# PwmOut.net
KiCad netlist of a schematic drawn in Altium Designer
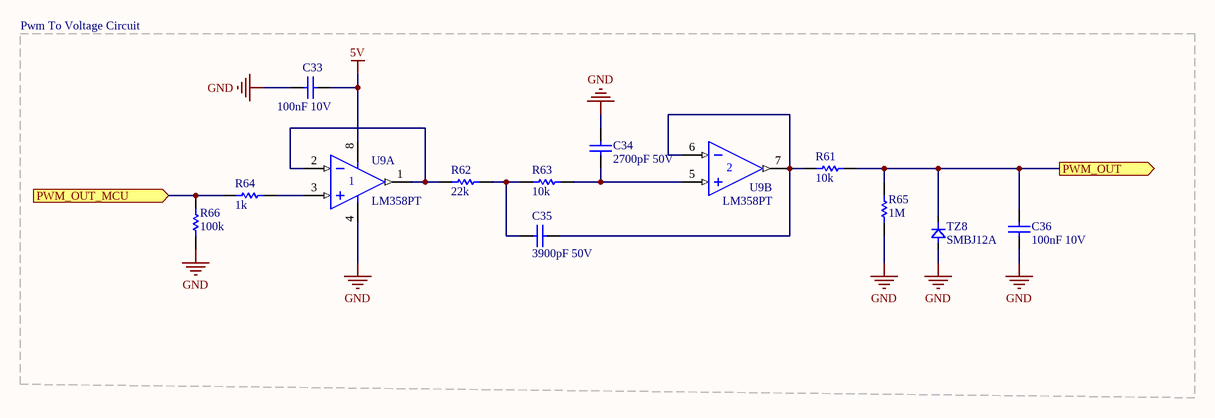
[diagram p0: PwmOut.SchDoc]

(export (version "E")
  (design (tool "Eeschema 10.0.6"))
  (components
    (comp (ref "C33")
      (value "100nF 10V")
      (footprint "0402")
      (description "Capacitor")
      (fields (field (name "PARTNUMBER") "CAP.100n.10V.20%.SMD.0402") (field (name "MANUFACTURER") "Wurth"))
      (libsource (lib "IntLib") (part "Cap"))
    )
    (comp (ref "C34")
      (value "2700pF 50V")
      (footprint "C0805")
      (description "Capacitor")
      (fields (field (name "PARTNUMBER") "CAP.2700p.50V.10%.SMD.0805") (field (name "MANUFACTURER") "Vishay"))
      (libsource (lib "IntLib") (part "Cap"))
    )
    (comp (ref "C35")
      (value "3900pF 50V")
      (footprint "C0805")
      (description "Capacitor")
      (fields (field (name "PARTNUMBER") "CAP.3900p.50V.5%.SMD.0805") (field (name "MANUFACTURER") "Vishay"))
      (libsource (lib "IntLib") (part "Cap"))
    )
    (comp (ref "C36")
      (value "100nF 10V")
      (footprint "C0805")
      (description "Capacitor")
      (fields (field (name "PARTNUMBER") "CAP.1u.10V.10%.SMD.0805") (field (name "MANUFACTURER") "Vishay"))
      (libsource (lib "IntLib") (part "Cap"))
    )
    (comp (ref "R61")
      (value "10k")
      (footprint "6-0805_M")
      (description "Resistor")
      (fields (field (name "PARTNUMBER") "RES.10K.1/8W.5%.SMD.0805") (field (name "MANUFACTURER") "Yageo"))
      (libsource (lib "IntLib") (part "Res"))
    )
    (comp (ref "R62")
      (value "22k")
      (footprint "6-0805_M")
      (description "Resistor")
      (fields (field (name "PARTNUMBER") "RES.22K.1/8W.5%.SMD.0805") (field (name "MANUFACTURER") "Bourns"))
      (libsource (lib "IntLib") (part "Res"))
    )
    (comp (ref "R63")
      (value "10k")
      (footprint "6-0805_M")
      (description "Resistor")
      (fields (field (name "PARTNUMBER") "RES.10K.1/8W.5%.SMD.0805") (field (name "MANUFACTURER") "Yageo"))
      (libsource (lib "IntLib") (part "Res"))
    )
    (comp (ref "R64")
      (value "1k")
      (footprint "6-0805_M")
      (description "Resistor")
      (fields (field (name "PARTNUMBER") "RES.1K.1/8W.5%.SMD.0805") (field (name "MANUFACTURER") "Yageo"))
      (libsource (lib "IntLib") (part "Res"))
    )
    (comp (ref "R65")
      (value "1M")
      (footprint "6-0805_M")
      (description "Resistor")
      (fields (field (name "PARTNUMBER") "RES.1M.1/8W.5%.SMD.0805") (field (name "MANUFACTURER") "Bourns"))
      (libsource (lib "IntLib") (part "Res"))
    )
    (comp (ref "R66")
      (value "100k")
      (footprint "6-0805_M")
      (description "Resistor")
      (fields (field (name "PARTNUMBER") "RES.100K.1/8W.5%.SMD.0805") (field (name "MANUFACTURER") "Yageo"))
      (libsource (lib "IntLib") (part "Res"))
    )
    (comp (ref "TZ8")
      (value "SMBJ12A")
      (footprint "DO-214AA")
      (description "ESD Suppressors / TVS Diodes 12V 600W SMB Unidirectional")
      (fields (field (name "MANUFACTURER") "ON Semiconductor"))
      (libsource (lib "IntLib") (part "SMBJ12A"))
    )
    (comp (ref "U9")
      (value "LM358PT")
      (footprint "TSOP-8")
      (description "Operational Amplifiers - Op Amps Dual Low Power")
      (fields (field (name "MANUFACTURER") "STMicroelectronics"))
      (libsource (lib "IntLib") (part "LM358PT"))
    )
  )
  (nets
    (net (code "1") (name "/PWM_OUT") (class "Default")
      (node (ref "C36") (pin "1") (pinfunction "1_1") (pintype "passive"))
      (node (ref "R61") (pin "2") (pinfunction "2_2") (pintype "passive"))
      (node (ref "R65") (pin "2") (pinfunction "2_2") (pintype "passive"))
      (node (ref "TZ8") (pin "2") (pinfunction "C_2") (pintype "passive"))
    )
    (net (code "2") (name "/PWM_OUT_MCU") (class "Default")
      (node (ref "R64") (pin "1") (pinfunction "1_1") (pintype "passive"))
      (node (ref "R66") (pin "2") (pinfunction "2_2") (pintype "passive"))
    )
    (net (code "3") (name "5V") (class "Default")
      (node (ref "C33") (pin "2") (pinfunction "2_2") (pintype "passive"))
      (node (ref "U9") (pin "8") (pinfunction "Vs+_8") (pintype "passive"))
    )
    (net (code "4") (name "GND") (class "Default")
      (node (ref "C33") (pin "1") (pinfunction "1_1") (pintype "passive"))
      (node (ref "C34") (pin "2") (pinfunction "2_2") (pintype "passive"))
      (node (ref "C36") (pin "2") (pinfunction "2_2") (pintype "passive"))
      (node (ref "R65") (pin "1") (pinfunction "1_1") (pintype "passive"))
      (node (ref "R66") (pin "1") (pinfunction "1_1") (pintype "passive"))
      (node (ref "TZ8") (pin "1") (pinfunction "A_1") (pintype "passive"))
      (node (ref "U9") (pin "4") (pinfunction "Vs-_4") (pintype "passive"))
    )
    (net (code "5") (name "Net-(C35-Pad1)") (class "Default")
      (node (ref "C35") (pin "1") (pinfunction "1_1") (pintype "passive"))
      (node (ref "R62") (pin "2") (pinfunction "2_2") (pintype "passive"))
      (node (ref "R63") (pin "1") (pinfunction "1_1") (pintype "passive"))
    )
    (net (code "6") (name "Net-(U9A-IN+)") (class "Default")
      (node (ref "R64") (pin "2") (pinfunction "2_2") (pintype "passive"))
      (node (ref "U9") (pin "3") (pinfunction "IN+_3") (pintype "input"))
    )
    (net (code "7") (name "Net-(U9A-IN-)") (class "Default")
      (node (ref "R62") (pin "1") (pinfunction "1_1") (pintype "passive"))
      (node (ref "U9") (pin "1") (pinfunction "OUT_1") (pintype "output"))
      (node (ref "U9") (pin "2") (pinfunction "IN-_2") (pintype "input"))
    )
    (net (code "8") (name "Net-(U9B-IN+)") (class "Default")
      (node (ref "C34") (pin "1") (pinfunction "1_1") (pintype "passive"))
      (node (ref "R63") (pin "2") (pinfunction "2_2") (pintype "passive"))
      (node (ref "U9") (pin "5") (pinfunction "IN+_5") (pintype "input"))
    )
    (net (code "9") (name "Net-(U9B-IN-)") (class "Default")
      (node (ref "C35") (pin "2") (pinfunction "2_2") (pintype "passive"))
      (node (ref "R61") (pin "1") (pinfunction "1_1") (pintype "passive"))
      (node (ref "U9") (pin "6") (pinfunction "IN-_6") (pintype "input"))
      (node (ref "U9") (pin "7") (pinfunction "OUT_7") (pintype "output"))
    )
  )
)
